# LoPoSwitchWiFI.net
KiCad netlist of a schematic drawn in EasyEDA
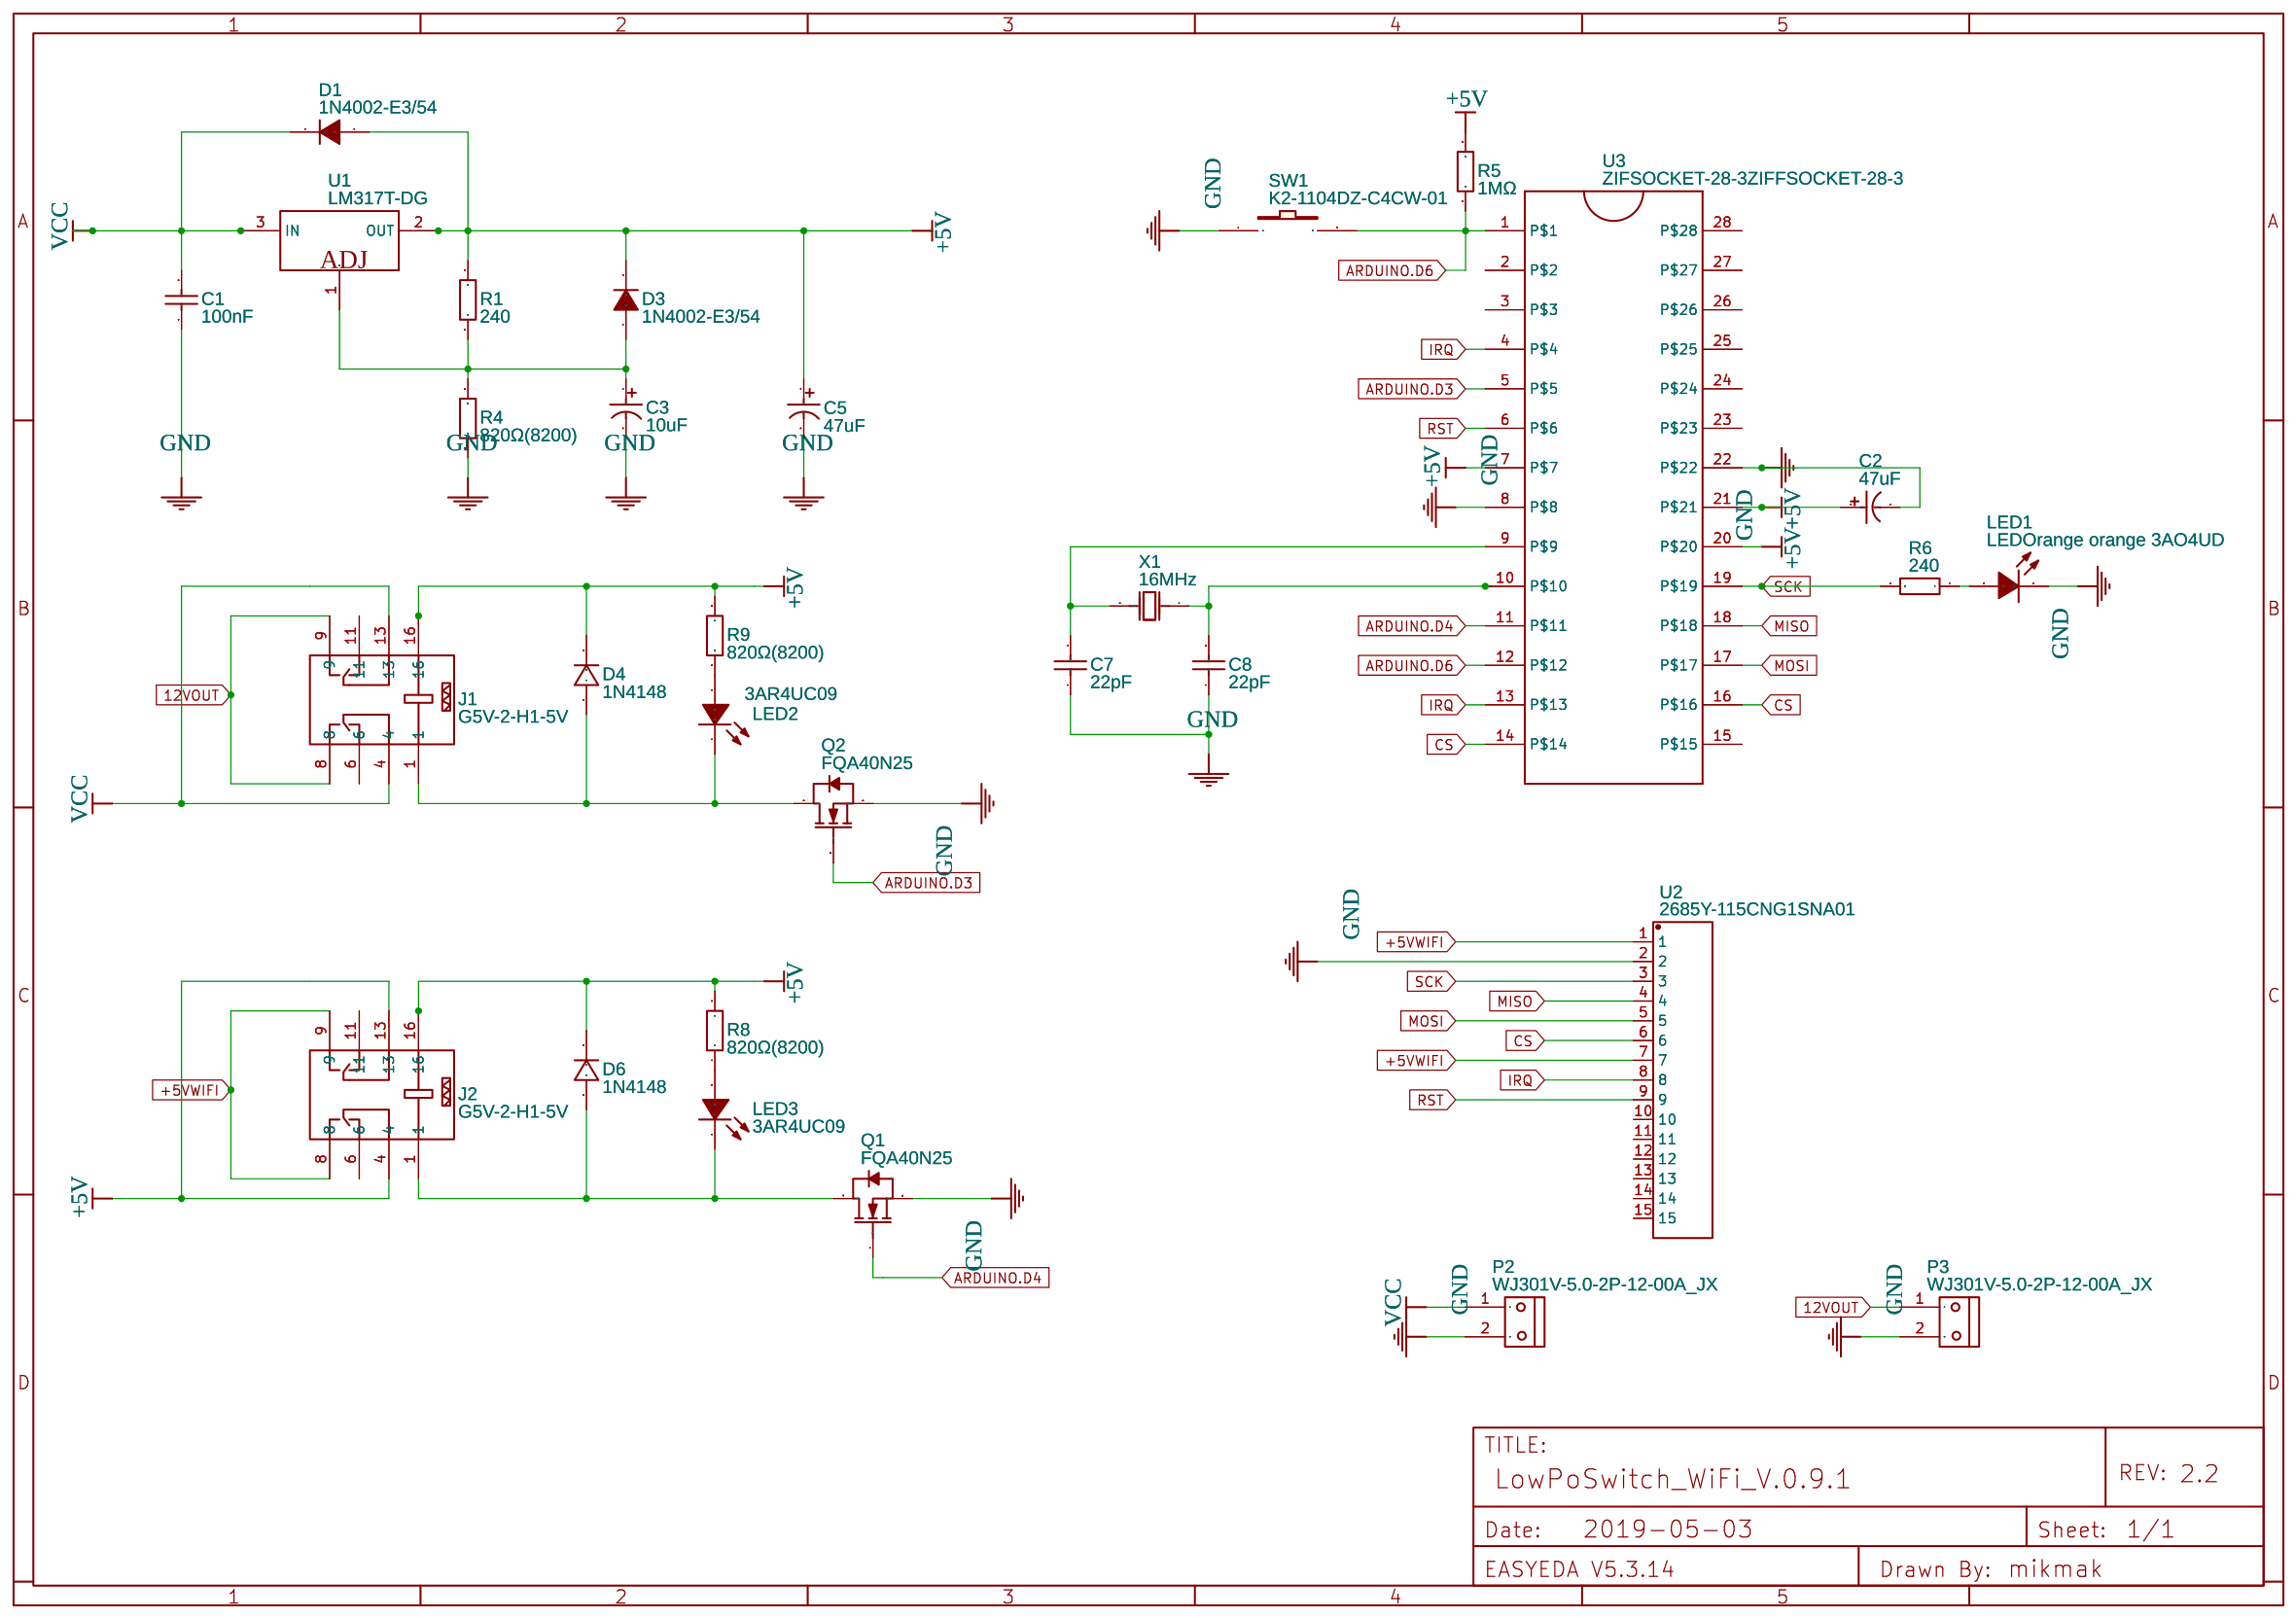
[diagram p0: schematic sheet]

(export (version "E")
  (design (tool "Eeschema 10.0.6"))
  (components
    (comp (ref "C1")
      (value "100nF")
      (fields
        (field (name "BOM_Manufacturer Part") "MPP104K5130508LC")
        (field (name "BOM_Supplier Part") "C109523")
      )
      (libsource (lib "") (part "MPP104K5130508LC"))
    )
    (comp (ref "C2")
      (value "47uF")
      (fields (field (name "BOM_Manufacturer Part") "47UF16V") (field (name "BOM_Supplier Part") "w"))
      (libsource (lib "") (part "47UF16V_1"))
    )
    (comp (ref "C3")
      (value "10uF")
      (fields (field (name "BOM_Manufacturer Part") "10uf/100V") (field (name "BOM_Supplier Part") "C2029"))
      (libsource (lib "") (part "10uf/100V"))
    )
    (comp (ref "C5")
      (value "47uF")
      (fields (field (name "BOM_Manufacturer Part") "47UF16V") (field (name "BOM_Supplier Part") "w"))
      (libsource (lib "") (part "47UF16V"))
    )
    (comp (ref "C7")
      (value "22pF")
      (fields
        (field (name "BOM_Manufacturer Part") "Monolithic0603N220J500")
        (field (name "BOM_Supplier Part") "C110283")
      )
      (libsource (lib "") (part "Monolithic0603N220J500"))
    )
    (comp (ref "C8")
      (value "22pF")
      (fields
        (field (name "BOM_Manufacturer Part") "Monolithic0603N220J500")
        (field (name "BOM_Supplier Part") "C110283")
      )
      (libsource (lib "") (part "Monolithic0603N220J500"))
    )
    (comp (ref "D1")
      (value "1N4002-E3/54")
      (fields (field (name "BOM_Supplier Part") "C33504"))
      (libsource (lib "") (part "Unknown_160_60"))
    )
    (comp (ref "D3")
      (value "1N4002-E3/54")
      (fields (field (name "BOM_Supplier Part") "C33504"))
      (libsource (lib "") (part "Unknown_310_145"))
    )
    (comp (ref "D4")
      (value "1N4148")
      (fields (field (name "BOM_Supplier Part") "C163750"))
      (libsource (lib "") (part "Unknown_290_335"))
    )
    (comp (ref "D6")
      (value "1N4148")
      (fields (field (name "BOM_Supplier Part") "C163750"))
      (libsource (lib "") (part "Unknown_290_535"))
    )
    (comp (ref "J1")
      (value "G5V-2-H1-5V")
      (fields (field (name "BOM_Supplier Part") "C28066"))
      (libsource (lib "") (part "Unknown_185_340"))
    )
    (comp (ref "J2")
      (value "G5V-2-H1-5V")
      (fields (field (name "BOM_Supplier Part") "C28066"))
      (libsource (lib "") (part "Unknown_185_540"))
    )
    (comp (ref "LED1")
      (value "LEDOrange orange 3AO4UD")
      (fields (field (name "BOM_Supplier Part") "C62095"))
      (libsource (lib "") (part "Unknown_1010_290"))
    )
    (comp (ref "LED2")
      (value "3AR4UC09")
      (fields (field (name "BOM_Supplier Part") "C6211"))
      (libsource (lib "") (part "Unknown_355_355"))
    )
    (comp (ref "LED3")
      (value "3AR4UC09")
      (fields (field (name "BOM_Supplier Part") "C6211"))
      (libsource (lib "") (part "Unknown_355_555"))
    )
    (comp (ref "P2")
      (value "WJ301V-5.0-2P-12-00A_JX")
      (fields (field (name "BOM_Manufacturer Part") "?") (field (name "BOM_Supplier Part") "C72326"))
      (libsource (lib "") (part "Unknown_755_655"))
    )
    (comp (ref "P3")
      (value "WJ301V-5.0-2P-12-00A_JX")
      (fields (field (name "BOM_Manufacturer Part") "?") (field (name "BOM_Supplier Part") "C72326"))
      (libsource (lib "") (part "Unknown_975_655"))
    )
    (comp (ref "Q1")
      (value "FQA40N25")
      (fields (field (name "BOM_Supplier Part") "C10877"))
      (libsource (lib "") (part "Unknown_435_610"))
    )
    (comp (ref "Q2")
      (value "FQA40N25")
      (fields (field (name "BOM_Supplier Part") "C10877"))
      (libsource (lib "") (part "Unknown_415_410"))
    )
    (comp (ref "R1")
      (value "240")
      (fields
        (field (name "BOM_Manufacturer Part") "MF1/8W-240Ω±1% T52")
        (field (name "BOM_Supplier Part") "C119165")
      )
      (libsource (lib "") (part "MF1/8W-240Ω±1% T52_1"))
    )
    (comp (ref "R4")
      (value "820Ω(8200)")
      (fields
        (field (name "BOM_Manufacturer Part") "MF1/8W-820Ω±1% T52")
        (field (name "BOM_Supplier Part") "C119177")
      )
      (libsource (lib "") (part "MF1/8W-820Ω±1% T52"))
    )
    (comp (ref "R5")
      (value "1MΩ")
      (fields
        (field (name "BOM_Manufacturer Part") "MFR0W4F1004A50")
        (field (name "BOM_Supplier Part") "C58596")
      )
      (libsource (lib "") (part "MFR0W4F1004A50"))
    )
    (comp (ref "R6")
      (value "240")
      (fields
        (field (name "BOM_Manufacturer Part") "MF1/8W-240Ω±1% T52")
        (field (name "BOM_Supplier Part") "C119165")
      )
      (libsource (lib "") (part "MF1/8W-240Ω±1% T52"))
    )
    (comp (ref "R8")
      (value "820Ω(8200)")
      (fields
        (field (name "BOM_Manufacturer Part") "MF1/8W-820Ω±1% T52")
        (field (name "BOM_Supplier Part") "C119177")
      )
      (libsource (lib "") (part "MF1/8W-820Ω±1% T52"))
    )
    (comp (ref "R9")
      (value "820Ω(8200)")
      (fields
        (field (name "BOM_Manufacturer Part") "MF1/8W-820Ω±1% T52")
        (field (name "BOM_Supplier Part") "C119177")
      )
      (libsource (lib "") (part "MF1/8W-820Ω±1% T52"))
    )
    (comp (ref "SW1")
      (value "K2-1104DZ-C4CW-01")
      (fields (field (name "BOM_Supplier Part") "C145889"))
      (libsource (lib "") (part "Unknown_640_110"))
    )
    (comp (ref "U1")
      (value "LM317T-DG")
      (fields (field (name "BOM_Supplier Part") "C18718"))
      (libsource (lib "") (part "Unknown_165_125"))
    )
    (comp (ref "U2")
      (value "2685Y-115CNG1SNA01")
      (fields (field (name "BOM_Supplier Part") "C350309"))
      (libsource (lib "") (part "Unknown_840_540"))
    )
    (comp (ref "U3")
      (value "ZIFSOCKET-28-3ZIFFSOCKET-28-3")
      (fields (field (name "BOM_Manufacturer Part") "?"))
      (libsource (lib "") (part "Unknown_765_390"))
    )
    (comp (ref "X1")
      (value "16MHz")
      (fields
        (field (name "BOM_Manufacturer Part") "X49SD16MSD2SC")
        (field (name "BOM_Supplier Part") "C16212")
      )
      (libsource (lib "") (part "X49SD16MSD2SC"))
    )
  )
  (nets
    (net (code "1") (name "+5V") (class "Default")
      (node (ref "C2") (pin "1") (pinfunction "1_1") (pintype "input"))
      (node (ref "C5") (pin "1") (pinfunction "1_1") (pintype "input"))
      (node (ref "D1") (pin "1") (pinfunction "A_1") (pintype "unspecified"))
      (node (ref "D3") (pin "2") (pinfunction "K_2") (pintype "unspecified"))
      (node (ref "D4") (pin "2") (pinfunction "2_2") (pintype "unspecified"))
      (node (ref "D6") (pin "2") (pinfunction "2_2") (pintype "unspecified"))
      (node (ref "J1") (pin "16") (pinfunction "16_16") (pintype "unspecified"))
      (node (ref "J2") (pin "13") (pinfunction "13_13") (pintype "unspecified"))
      (node (ref "J2") (pin "16") (pinfunction "16_16") (pintype "unspecified"))
      (node (ref "J2") (pin "4") (pinfunction "4_4") (pintype "unspecified"))
      (node (ref "R1") (pin "2") (pinfunction "2_2") (pintype "input"))
      (node (ref "R5") (pin "2") (pinfunction "2_2") (pintype "input"))
      (node (ref "R8") (pin "2") (pinfunction "2_2") (pintype "input"))
      (node (ref "R9") (pin "2") (pinfunction "2_2") (pintype "input"))
      (node (ref "U1") (pin "2") (pinfunction "OUT_2") (pintype "passive"))
      (node (ref "U3") (pin "20") (pinfunction "P$20_20") (pintype "unspecified"))
      (node (ref "U3") (pin "21") (pinfunction "P$21_21") (pintype "unspecified"))
      (node (ref "U3") (pin "7") (pinfunction "P$7_7") (pintype "unspecified"))
    )
    (net (code "2") (name "+5VWIFI") (class "Default")
      (node (ref "J2") (pin "8") (pinfunction "8_8") (pintype "unspecified"))
      (node (ref "J2") (pin "9") (pinfunction "9_9") (pintype "unspecified"))
      (node (ref "U2") (pin "1") (pinfunction "1_1") (pintype "unspecified"))
      (node (ref "U2") (pin "7") (pinfunction "7_7") (pintype "unspecified"))
    )
    (net (code "3") (name "12VOUT") (class "Default")
      (node (ref "J1") (pin "8") (pinfunction "8_8") (pintype "unspecified"))
      (node (ref "J1") (pin "9") (pinfunction "9_9") (pintype "unspecified"))
      (node (ref "P3") (pin "1") (pinfunction "1_1") (pintype "unspecified"))
    )
    (net (code "4") (name "ARDUINO.D3") (class "Default")
      (node (ref "Q2") (pin "1") (pinfunction "G_1") (pintype "unspecified"))
      (node (ref "U3") (pin "5") (pinfunction "P$5_5") (pintype "unspecified"))
    )
    (net (code "5") (name "ARDUINO.D4") (class "Default")
      (node (ref "Q1") (pin "1") (pinfunction "G_1") (pintype "unspecified"))
      (node (ref "U3") (pin "11") (pinfunction "P$11_11") (pintype "unspecified"))
    )
    (net (code "6") (name "ARDUINO.D6") (class "Default")
      (node (ref "R5") (pin "1") (pinfunction "1_1") (pintype "input"))
      (node (ref "SW1") (pin "2") (pinfunction "2_2") (pintype "input"))
      (node (ref "U3") (pin "1") (pinfunction "P$1_1") (pintype "unspecified"))
      (node (ref "U3") (pin "12") (pinfunction "P$12_12") (pintype "unspecified"))
    )
    (net (code "7") (name "CS") (class "Default")
      (node (ref "U2") (pin "6") (pinfunction "6_6") (pintype "unspecified"))
      (node (ref "U3") (pin "14") (pinfunction "P$14_14") (pintype "unspecified"))
      (node (ref "U3") (pin "16") (pinfunction "P$16_16") (pintype "unspecified"))
    )
    (net (code "8") (name "GND") (class "Default")
      (node (ref "C1") (pin "1") (pinfunction "1_1") (pintype "input"))
      (node (ref "C2") (pin "2") (pinfunction "2_2") (pintype "input"))
      (node (ref "C3") (pin "2") (pinfunction "2_2") (pintype "input"))
      (node (ref "C5") (pin "2") (pinfunction "2_2") (pintype "input"))
      (node (ref "C7") (pin "1") (pinfunction "1_1") (pintype "input"))
      (node (ref "C8") (pin "1") (pinfunction "1_1") (pintype "input"))
      (node (ref "LED1") (pin "1") (pinfunction "K_1") (pintype "unspecified"))
      (node (ref "P2") (pin "2") (pinfunction "2_2") (pintype "unspecified"))
      (node (ref "P3") (pin "2") (pinfunction "2_2") (pintype "unspecified"))
      (node (ref "Q1") (pin "3") (pinfunction "S_3") (pintype "unspecified"))
      (node (ref "Q2") (pin "3") (pinfunction "S_3") (pintype "unspecified"))
      (node (ref "R4") (pin "1") (pinfunction "1_1") (pintype "input"))
      (node (ref "SW1") (pin "1") (pinfunction "1_1") (pintype "input"))
      (node (ref "U2") (pin "2") (pinfunction "2_2") (pintype "unspecified"))
      (node (ref "U3") (pin "22") (pinfunction "P$22_22") (pintype "unspecified"))
      (node (ref "U3") (pin "8") (pinfunction "P$8_8") (pintype "unspecified"))
    )
    (net (code "9") (name "IRQ") (class "Default")
      (node (ref "U2") (pin "8") (pinfunction "8_8") (pintype "unspecified"))
      (node (ref "U3") (pin "13") (pinfunction "P$13_13") (pintype "unspecified"))
      (node (ref "U3") (pin "4") (pinfunction "P$4_4") (pintype "unspecified"))
    )
    (net (code "10") (name "MISO") (class "Default")
      (node (ref "U2") (pin "4") (pinfunction "4_4") (pintype "unspecified"))
      (node (ref "U3") (pin "18") (pinfunction "P$18_18") (pintype "unspecified"))
    )
    (net (code "11") (name "MOSI") (class "Default")
      (node (ref "U2") (pin "5") (pinfunction "5_5") (pintype "unspecified"))
      (node (ref "U3") (pin "17") (pinfunction "P$17_17") (pintype "unspecified"))
    )
    (net (code "12") (name "Net-(D3-A)") (class "Default")
      (node (ref "C3") (pin "1") (pinfunction "1_1") (pintype "input"))
      (node (ref "D3") (pin "1") (pinfunction "A_1") (pintype "unspecified"))
      (node (ref "R1") (pin "1") (pinfunction "1_1") (pintype "input"))
      (node (ref "R4") (pin "2") (pinfunction "2_2") (pintype "input"))
      (node (ref "U1") (pin "1") (pinfunction "ADJ_1") (pintype "unspecified"))
    )
    (net (code "13") (name "Net-(LED1-A)") (class "Default")
      (node (ref "LED1") (pin "2") (pinfunction "A_2") (pintype "unspecified"))
      (node (ref "R6") (pin "1") (pinfunction "1_1") (pintype "input"))
    )
    (net (code "14") (name "Net-(LED2-A)") (class "Default")
      (node (ref "LED2") (pin "2") (pinfunction "A_2") (pintype "unspecified"))
      (node (ref "R9") (pin "1") (pinfunction "1_1") (pintype "input"))
    )
    (net (code "15") (name "Net-(LED2-K)") (class "Default")
      (node (ref "D4") (pin "1") (pinfunction "1_1") (pintype "unspecified"))
      (node (ref "J1") (pin "1") (pinfunction "1_1") (pintype "unspecified"))
      (node (ref "LED2") (pin "1") (pinfunction "K_1") (pintype "unspecified"))
      (node (ref "Q2") (pin "2") (pinfunction "D_2") (pintype "unspecified"))
    )
    (net (code "16") (name "Net-(LED3-A)") (class "Default")
      (node (ref "LED3") (pin "2") (pinfunction "A_2") (pintype "unspecified"))
      (node (ref "R8") (pin "1") (pinfunction "1_1") (pintype "input"))
    )
    (net (code "17") (name "Net-(LED3-K)") (class "Default")
      (node (ref "D6") (pin "1") (pinfunction "1_1") (pintype "unspecified"))
      (node (ref "J2") (pin "1") (pinfunction "1_1") (pintype "unspecified"))
      (node (ref "LED3") (pin "1") (pinfunction "K_1") (pintype "unspecified"))
      (node (ref "Q1") (pin "2") (pinfunction "D_2") (pintype "unspecified"))
    )
    (net (code "18") (name "Net-(U3-P$9)") (class "Default")
      (node (ref "C7") (pin "2") (pinfunction "2_2") (pintype "input"))
      (node (ref "U3") (pin "9") (pinfunction "P$9_9") (pintype "unspecified"))
      (node (ref "X1") (pin "2") (pinfunction "OSC2_2") (pintype "input"))
    )
    (net (code "19") (name "Net-(U3-P$10)") (class "Default")
      (node (ref "C8") (pin "2") (pinfunction "2_2") (pintype "input"))
      (node (ref "U3") (pin "10") (pinfunction "P$10_10") (pintype "unspecified"))
      (node (ref "X1") (pin "1") (pinfunction "OSC1_1") (pintype "input"))
    )
    (net (code "20") (name "RST") (class "Default")
      (node (ref "U2") (pin "9") (pinfunction "9_9") (pintype "unspecified"))
      (node (ref "U3") (pin "6") (pinfunction "P$6_6") (pintype "unspecified"))
    )
    (net (code "21") (name "SCK") (class "Default")
      (node (ref "R6") (pin "2") (pinfunction "2_2") (pintype "input"))
      (node (ref "U2") (pin "3") (pinfunction "3_3") (pintype "unspecified"))
      (node (ref "U3") (pin "19") (pinfunction "P$19_19") (pintype "unspecified"))
    )
    (net (code "22") (name "VCC") (class "Default")
      (node (ref "C1") (pin "2") (pinfunction "2_2") (pintype "input"))
      (node (ref "D1") (pin "2") (pinfunction "K_2") (pintype "unspecified"))
      (node (ref "J1") (pin "13") (pinfunction "13_13") (pintype "unspecified"))
      (node (ref "J1") (pin "4") (pinfunction "4_4") (pintype "unspecified"))
      (node (ref "P2") (pin "1") (pinfunction "1_1") (pintype "unspecified"))
      (node (ref "U1") (pin "3") (pinfunction "IN_3") (pintype "passive"))
    )
    (net (code "23") (name "unconnected-(J1-Pad6)") (class "Default")
      (node (ref "J1") (pin "6") (pinfunction "6_6") (pintype "unspecified"))
    )
    (net (code "24") (name "unconnected-(J1-Pad11)") (class "Default")
      (node (ref "J1") (pin "11") (pinfunction "11_11") (pintype "unspecified"))
    )
    (net (code "25") (name "unconnected-(J2-Pad6)") (class "Default")
      (node (ref "J2") (pin "6") (pinfunction "6_6") (pintype "unspecified"))
    )
    (net (code "26") (name "unconnected-(J2-Pad11)") (class "Default")
      (node (ref "J2") (pin "11") (pinfunction "11_11") (pintype "unspecified"))
    )
    (net (code "27") (name "unconnected-(U2-Pad10)") (class "Default")
      (node (ref "U2") (pin "10") (pinfunction "10_10") (pintype "unspecified"))
    )
    (net (code "28") (name "unconnected-(U2-Pad11)") (class "Default")
      (node (ref "U2") (pin "11") (pinfunction "11_11") (pintype "unspecified"))
    )
    (net (code "29") (name "unconnected-(U2-Pad12)") (class "Default")
      (node (ref "U2") (pin "12") (pinfunction "12_12") (pintype "unspecified"))
    )
    (net (code "30") (name "unconnected-(U2-Pad13)") (class "Default")
      (node (ref "U2") (pin "13") (pinfunction "13_13") (pintype "unspecified"))
    )
    (net (code "31") (name "unconnected-(U2-Pad14)") (class "Default")
      (node (ref "U2") (pin "14") (pinfunction "14_14") (pintype "unspecified"))
    )
    (net (code "32") (name "unconnected-(U2-Pad15)") (class "Default")
      (node (ref "U2") (pin "15") (pinfunction "15_15") (pintype "unspecified"))
    )
    (net (code "33") (name "unconnected-(U3-P$2-Pad2)") (class "Default")
      (node (ref "U3") (pin "2") (pinfunction "P$2_2") (pintype "unspecified"))
    )
    (net (code "34") (name "unconnected-(U3-P$3-Pad3)") (class "Default")
      (node (ref "U3") (pin "3") (pinfunction "P$3_3") (pintype "unspecified"))
    )
    (net (code "35") (name "unconnected-(U3-P$15-Pad15)") (class "Default")
      (node (ref "U3") (pin "15") (pinfunction "P$15_15") (pintype "unspecified"))
    )
    (net (code "36") (name "unconnected-(U3-P$23-Pad23)") (class "Default")
      (node (ref "U3") (pin "23") (pinfunction "P$23_23") (pintype "unspecified"))
    )
    (net (code "37") (name "unconnected-(U3-P$24-Pad24)") (class "Default")
      (node (ref "U3") (pin "24") (pinfunction "P$24_24") (pintype "unspecified"))
    )
    (net (code "38") (name "unconnected-(U3-P$25-Pad25)") (class "Default")
      (node (ref "U3") (pin "25") (pinfunction "P$25_25") (pintype "unspecified"))
    )
    (net (code "39") (name "unconnected-(U3-P$26-Pad26)") (class "Default")
      (node (ref "U3") (pin "26") (pinfunction "P$26_26") (pintype "unspecified"))
    )
    (net (code "40") (name "unconnected-(U3-P$27-Pad27)") (class "Default")
      (node (ref "U3") (pin "27") (pinfunction "P$27_27") (pintype "unspecified"))
    )
    (net (code "41") (name "unconnected-(U3-P$28-Pad28)") (class "Default")
      (node (ref "U3") (pin "28") (pinfunction "P$28_28") (pintype "unspecified"))
    )
  )
)
